# IMUs.net
KiCad netlist of a schematic drawn in Altium Designer
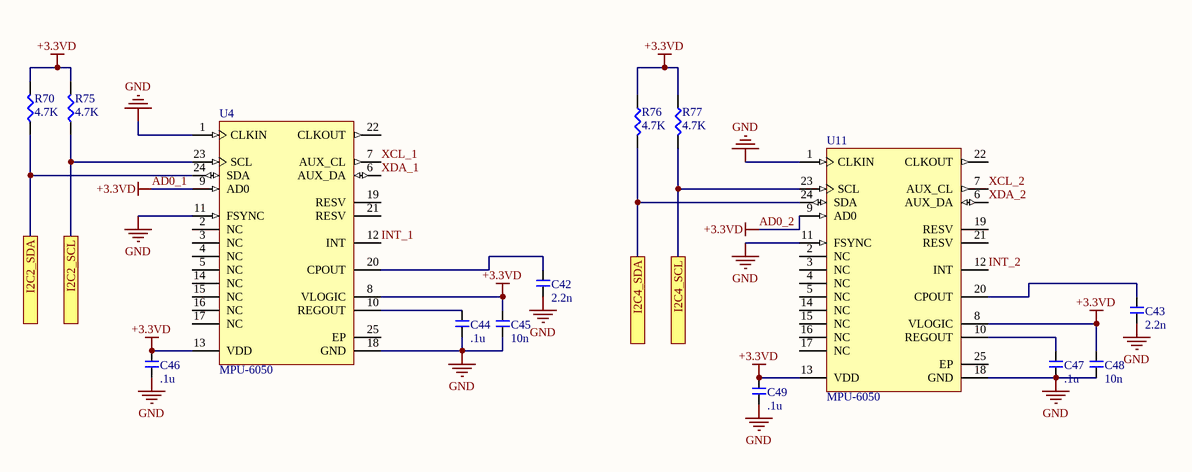
[diagram p0: IMUs.SchDoc]

(export (version "E")
  (design (tool "Eeschema 10.0.6"))
  (components
    (comp (ref "C42")
      (value "2.2n")
      (footprint "CAP-0603")
      (libsource (lib "ife19_Elec_Library") (part "CAP-0603"))
    )
    (comp (ref "C43")
      (value "2.2n")
      (footprint "CAP-0603")
      (libsource (lib "ife19_Elec_Library") (part "CAP-0603"))
    )
    (comp (ref "C44")
      (value ".1u")
      (footprint "CAP-0603")
      (libsource (lib "ife19_Elec_Library") (part "CAP-0603"))
    )
    (comp (ref "C45")
      (value "10n")
      (footprint "CAP-0603")
      (libsource (lib "ife19_Elec_Library") (part "CAP-0603"))
    )
    (comp (ref "C46")
      (value ".1u")
      (footprint "CAP-0603")
      (libsource (lib "ife19_Elec_Library") (part "CAP-0603"))
    )
    (comp (ref "C47")
      (value ".1u")
      (footprint "CAP-0603")
      (libsource (lib "ife19_Elec_Library") (part "CAP-0603"))
    )
    (comp (ref "C48")
      (value "10n")
      (footprint "CAP-0603")
      (libsource (lib "ife19_Elec_Library") (part "CAP-0603"))
    )
    (comp (ref "C49")
      (value ".1u")
      (footprint "CAP-0603")
      (libsource (lib "ife19_Elec_Library") (part "CAP-0603"))
    )
    (comp (ref "R70")
      (value "4.7K")
      (footprint "RES-0603")
      (libsource (lib "ife19_Elec_Library") (part "RES-0603"))
    )
    (comp (ref "R75")
      (value "4.7K")
      (footprint "RES-0603")
      (libsource (lib "ife19_Elec_Library") (part "RES-0603"))
    )
    (comp (ref "R76")
      (value "4.7K")
      (footprint "RES-0603")
      (libsource (lib "ife19_Elec_Library") (part "RES-0603"))
    )
    (comp (ref "R77")
      (value "4.7K")
      (footprint "RES-0603")
      (libsource (lib "ife19_Elec_Library") (part "RES-0603"))
    )
    (comp (ref "U4")
      (value "MPU-6050")
      (footprint "IS-QFN-24_V")
      (fields (field (name "MANUFACTURER") "InvenSense"))
      (libsource (lib "Altium Content Vault") (part "IS-MPU-6050-QFN-24"))
    )
    (comp (ref "U11")
      (value "MPU-6050")
      (footprint "IS-QFN-24_V")
      (fields (field (name "MANUFACTURER") "InvenSense"))
      (libsource (lib "Altium Content Vault") (part "IS-MPU-6050-QFN-24"))
    )
  )
  (nets
    (net (code "1") (name "+3.3VD") (class "Default")
      (node (ref "C45") (pin "2") (pinfunction "2_2") (pintype "passive"))
      (node (ref "C46") (pin "2") (pinfunction "2_2") (pintype "passive"))
      (node (ref "C48") (pin "2") (pinfunction "2_2") (pintype "passive"))
      (node (ref "C49") (pin "2") (pinfunction "2_2") (pintype "passive"))
      (node (ref "R70") (pin "2") (pinfunction "2_2") (pintype "passive"))
      (node (ref "R75") (pin "2") (pinfunction "2_2") (pintype "passive"))
      (node (ref "R76") (pin "1") (pinfunction "1_1") (pintype "passive"))
      (node (ref "R77") (pin "1") (pinfunction "1_1") (pintype "passive"))
      (node (ref "U11") (pin "13") (pinfunction "VDD_13") (pintype "power_in"))
      (node (ref "U11") (pin "8") (pinfunction "VLOGIC_8") (pintype "power_in"))
      (node (ref "U11") (pin "9") (pinfunction "AD0_9") (pintype "input"))
      (node (ref "U4") (pin "13") (pinfunction "VDD_13") (pintype "power_in"))
      (node (ref "U4") (pin "8") (pinfunction "VLOGIC_8") (pintype "power_in"))
      (node (ref "U4") (pin "9") (pinfunction "AD0_9") (pintype "input"))
    )
    (net (code "2") (name "/I2C2_SCL") (class "Default")
      (node (ref "R75") (pin "1") (pinfunction "1_1") (pintype "passive"))
      (node (ref "U4") (pin "23") (pinfunction "SCL_23") (pintype "input"))
    )
    (net (code "3") (name "/I2C2_SDA") (class "Default")
      (node (ref "R70") (pin "1") (pinfunction "1_1") (pintype "passive"))
      (node (ref "U4") (pin "24") (pinfunction "SDA_24") (pintype "bidirectional"))
    )
    (net (code "4") (name "/I2C4_SCL") (class "Default")
      (node (ref "R77") (pin "2") (pinfunction "2_2") (pintype "passive"))
      (node (ref "U11") (pin "23") (pinfunction "SCL_23") (pintype "input"))
    )
    (net (code "5") (name "/I2C4_SDA") (class "Default")
      (node (ref "R76") (pin "2") (pinfunction "2_2") (pintype "passive"))
      (node (ref "U11") (pin "24") (pinfunction "SDA_24") (pintype "bidirectional"))
    )
    (net (code "6") (name "/INT_1") (class "Default")
      (node (ref "U4") (pin "12") (pinfunction "INT_12") (pintype "open_collector"))
    )
    (net (code "7") (name "/INT_2") (class "Default")
      (node (ref "U11") (pin "12") (pinfunction "INT_12") (pintype "open_collector"))
    )
    (net (code "8") (name "/XCL_1") (class "Default")
      (node (ref "U4") (pin "7") (pinfunction "AUX_CL_7") (pintype "output"))
    )
    (net (code "9") (name "/XCL_2") (class "Default")
      (node (ref "U11") (pin "7") (pinfunction "AUX_CL_7") (pintype "output"))
    )
    (net (code "10") (name "/XDA_1") (class "Default")
      (node (ref "U4") (pin "6") (pinfunction "AUX_DA_6") (pintype "bidirectional"))
    )
    (net (code "11") (name "/XDA_2") (class "Default")
      (node (ref "U11") (pin "6") (pinfunction "AUX_DA_6") (pintype "bidirectional"))
    )
    (net (code "12") (name "GND") (class "Default")
      (node (ref "C42") (pin "1") (pinfunction "1_1") (pintype "passive"))
      (node (ref "C43") (pin "1") (pinfunction "1_1") (pintype "passive"))
      (node (ref "C44") (pin "1") (pinfunction "1_1") (pintype "passive"))
      (node (ref "C45") (pin "1") (pinfunction "1_1") (pintype "passive"))
      (node (ref "C46") (pin "1") (pinfunction "1_1") (pintype "passive"))
      (node (ref "C47") (pin "1") (pinfunction "1_1") (pintype "passive"))
      (node (ref "C48") (pin "1") (pinfunction "1_1") (pintype "passive"))
      (node (ref "C49") (pin "1") (pinfunction "1_1") (pintype "passive"))
      (node (ref "U11") (pin "1") (pinfunction "CLKIN_1") (pintype "input"))
      (node (ref "U11") (pin "11") (pinfunction "FSYNC_11") (pintype "input"))
      (node (ref "U11") (pin "18") (pinfunction "GND_18") (pintype "power_in"))
      (node (ref "U4") (pin "1") (pinfunction "CLKIN_1") (pintype "input"))
      (node (ref "U4") (pin "11") (pinfunction "FSYNC_11") (pintype "input"))
      (node (ref "U4") (pin "18") (pinfunction "GND_18") (pintype "power_in"))
    )
    (net (code "13") (name "Net-(U4-CPOUT)") (class "Default")
      (node (ref "C42") (pin "2") (pinfunction "2_2") (pintype "passive"))
      (node (ref "U4") (pin "20") (pinfunction "CPOUT_20") (pintype "passive"))
    )
    (net (code "14") (name "Net-(U4-REGOUT)") (class "Default")
      (node (ref "C44") (pin "2") (pinfunction "2_2") (pintype "passive"))
      (node (ref "U4") (pin "10") (pinfunction "REGOUT_10") (pintype "passive"))
    )
    (net (code "15") (name "Net-(U11-CPOUT)") (class "Default")
      (node (ref "C43") (pin "2") (pinfunction "2_2") (pintype "passive"))
      (node (ref "U11") (pin "20") (pinfunction "CPOUT_20") (pintype "passive"))
    )
    (net (code "16") (name "Net-(U11-REGOUT)") (class "Default")
      (node (ref "C47") (pin "2") (pinfunction "2_2") (pintype "passive"))
      (node (ref "U11") (pin "10") (pinfunction "REGOUT_10") (pintype "passive"))
    )
    (net (code "17") (name "unconnected-(U4-CLKOUT-Pad22)") (class "Default")
      (node (ref "U4") (pin "22") (pinfunction "CLKOUT_22") (pintype "output"))
    )
    (net (code "18") (name "unconnected-(U4-EP-Pad25)") (class "Default")
      (node (ref "U4") (pin "25") (pinfunction "EP_25") (pintype "power_in"))
    )
    (net (code "19") (name "unconnected-(U4-NC-Pad2)") (class "Default")
      (node (ref "U4") (pin "2") (pinfunction "NC_2") (pintype "passive"))
    )
    (net (code "20") (name "unconnected-(U4-NC-Pad3)") (class "Default")
      (node (ref "U4") (pin "3") (pinfunction "NC_3") (pintype "passive"))
    )
    (net (code "21") (name "unconnected-(U4-NC-Pad4)") (class "Default")
      (node (ref "U4") (pin "4") (pinfunction "NC_4") (pintype "passive"))
    )
    (net (code "22") (name "unconnected-(U4-NC-Pad5)") (class "Default")
      (node (ref "U4") (pin "5") (pinfunction "NC_5") (pintype "passive"))
    )
    (net (code "23") (name "unconnected-(U4-NC-Pad14)") (class "Default")
      (node (ref "U4") (pin "14") (pinfunction "NC_14") (pintype "passive"))
    )
    (net (code "24") (name "unconnected-(U4-NC-Pad15)") (class "Default")
      (node (ref "U4") (pin "15") (pinfunction "NC_15") (pintype "passive"))
    )
    (net (code "25") (name "unconnected-(U4-NC-Pad16)") (class "Default")
      (node (ref "U4") (pin "16") (pinfunction "NC_16") (pintype "passive"))
    )
    (net (code "26") (name "unconnected-(U4-NC-Pad17)") (class "Default")
      (node (ref "U4") (pin "17") (pinfunction "NC_17") (pintype "passive"))
    )
    (net (code "27") (name "unconnected-(U4-RESV-Pad19)") (class "Default")
      (node (ref "U4") (pin "19") (pinfunction "RESV_19") (pintype "passive"))
    )
    (net (code "28") (name "unconnected-(U4-RESV-Pad21)") (class "Default")
      (node (ref "U4") (pin "21") (pinfunction "RESV_21") (pintype "passive"))
    )
    (net (code "29") (name "unconnected-(U11-CLKOUT-Pad22)") (class "Default")
      (node (ref "U11") (pin "22") (pinfunction "CLKOUT_22") (pintype "output"))
    )
    (net (code "30") (name "unconnected-(U11-EP-Pad25)") (class "Default")
      (node (ref "U11") (pin "25") (pinfunction "EP_25") (pintype "power_in"))
    )
    (net (code "31") (name "unconnected-(U11-NC-Pad2)") (class "Default")
      (node (ref "U11") (pin "2") (pinfunction "NC_2") (pintype "passive"))
    )
    (net (code "32") (name "unconnected-(U11-NC-Pad3)") (class "Default")
      (node (ref "U11") (pin "3") (pinfunction "NC_3") (pintype "passive"))
    )
    (net (code "33") (name "unconnected-(U11-NC-Pad4)") (class "Default")
      (node (ref "U11") (pin "4") (pinfunction "NC_4") (pintype "passive"))
    )
    (net (code "34") (name "unconnected-(U11-NC-Pad5)") (class "Default")
      (node (ref "U11") (pin "5") (pinfunction "NC_5") (pintype "passive"))
    )
    (net (code "35") (name "unconnected-(U11-NC-Pad14)") (class "Default")
      (node (ref "U11") (pin "14") (pinfunction "NC_14") (pintype "passive"))
    )
    (net (code "36") (name "unconnected-(U11-NC-Pad15)") (class "Default")
      (node (ref "U11") (pin "15") (pinfunction "NC_15") (pintype "passive"))
    )
    (net (code "37") (name "unconnected-(U11-NC-Pad16)") (class "Default")
      (node (ref "U11") (pin "16") (pinfunction "NC_16") (pintype "passive"))
    )
    (net (code "38") (name "unconnected-(U11-NC-Pad17)") (class "Default")
      (node (ref "U11") (pin "17") (pinfunction "NC_17") (pintype "passive"))
    )
    (net (code "39") (name "unconnected-(U11-RESV-Pad19)") (class "Default")
      (node (ref "U11") (pin "19") (pinfunction "RESV_19") (pintype "passive"))
    )
    (net (code "40") (name "unconnected-(U11-RESV-Pad21)") (class "Default")
      (node (ref "U11") (pin "21") (pinfunction "RESV_21") (pintype "passive"))
    )
  )
)
